# power.net
KiCad netlist of a schematic drawn in Altium Designer
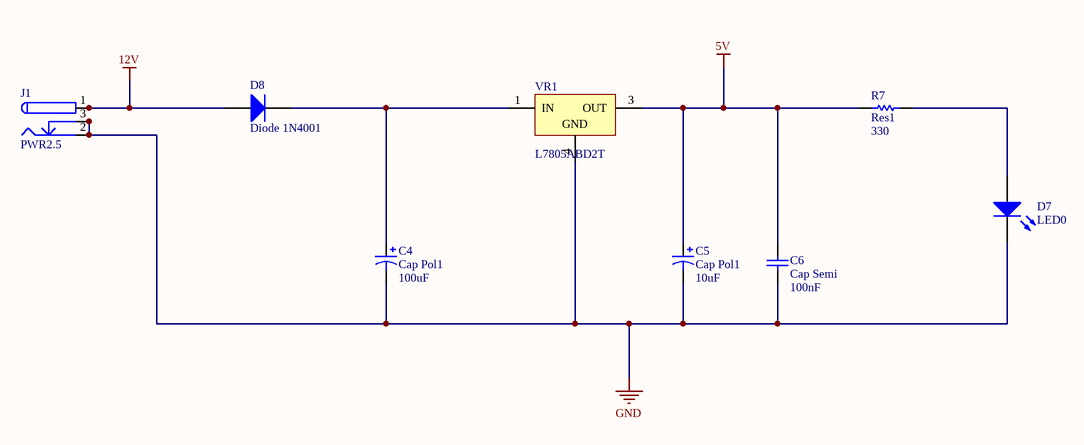
[diagram p0: power.SchDoc]

(export (version "E")
  (design (tool "Eeschema 10.0.6"))
  (components
    (comp (ref "C4")
      (value "Cap Pol1")
      (footprint "RB7.6-15")
      (description "Polarized Capacitor (Radial)")
      (fields (field (name "ALTIUM_VALUE") "100uF") (field (name "PUBLISHER") "Altium Limited"))
      (libsource (lib "Miscellaneous Devices") (part "Cap Pol1"))
    )
    (comp (ref "C5")
      (value "Cap Pol1")
      (footprint "RB7.6-15")
      (description "Polarized Capacitor (Radial)")
      (fields (field (name "ALTIUM_VALUE") "10uF") (field (name "PUBLISHER") "Altium Limited"))
      (libsource (lib "Miscellaneous Devices") (part "Cap Pol1"))
    )
    (comp (ref "C6")
      (value "Cap Semi")
      (footprint "C1206")
      (description "Capacitor (Semiconductor SIM Model)")
      (fields (field (name "ALTIUM_VALUE") "100nF") (field (name "PUBLISHER") "Altium Limited"))
      (libsource (lib "Miscellaneous Devices") (part "Cap Semi"))
    )
    (comp (ref "D7")
      (value "LED0")
      (footprint "LED-0")
      (description "Typical INFRARED GaAs LED")
      (fields (field (name "PUBLISHER") "Altium Limited"))
      (libsource (lib "Miscellaneous Devices") (part "LED0"))
    )
    (comp (ref "D8")
      (value "Diode 1N4001")
      (footprint "DO-41")
      (description "1 Amp General Purpose Rectifier")
      (fields (field (name "PUBLISHER") "Altium Limited"))
      (libsource (lib "Miscellaneous Devices") (part "Diode 1N4001"))
    )
    (comp (ref "J1")
      (value "PWR2.5")
      (footprint "KLD-0202")
      (description "Low Voltage Power Supply Connector")
      (fields (field (name "PUBLISHER") "Altium Limited"))
      (libsource (lib "Miscellaneous Connectors") (part "PWR2.5"))
    )
    (comp (ref "R7")
      (value "Res1")
      (footprint "AXIAL-0.3")
      (description "Resistor")
      (fields (field (name "ALTIUM_VALUE") "330") (field (name "PUBLISHER") "Altium Limited"))
      (libsource (lib "Miscellaneous Devices") (part "Res1"))
    )
    (comp (ref "VR1")
      (value "L7805ABD2T")
      (footprint "TO-263")
      (description "Precision 1A Regulator")
      (fields (field (name "PUBLISHER") "Altium Limited"))
      (libsource (lib "ST Power Mgt Voltage Regulator") (part "L7805ABD2T"))
    )
  )
  (nets
    (net (code "1") (name "5V") (class "Default")
      (node (ref "C5") (pin "1") (pinfunction "1_1") (pintype "passive"))
      (node (ref "C6") (pin "2") (pinfunction "2_2") (pintype "passive"))
      (node (ref "R7") (pin "1") (pinfunction "1_1") (pintype "passive"))
      (node (ref "VR1") (pin "3") (pinfunction "OUT_3") (pintype "power_in"))
    )
    (net (code "2") (name "12V") (class "Default")
      (node (ref "D8") (pin "1") (pinfunction "A_1") (pintype "passive"))
      (node (ref "J1") (pin "1") (pinfunction "1_1") (pintype "power_in"))
      (node (ref "J1") (pin "1A") (pinfunction "1A_1A") (pintype "power_in"))
      (node (ref "J1") (pin "1B") (pinfunction "1B_1B") (pintype "power_in"))
    )
    (net (code "3") (name "GND") (class "Default")
      (node (ref "C4") (pin "2") (pinfunction "2_2") (pintype "passive"))
      (node (ref "C5") (pin "2") (pinfunction "2_2") (pintype "passive"))
      (node (ref "C6") (pin "1") (pinfunction "1_1") (pintype "passive"))
      (node (ref "D7") (pin "2") (pinfunction "K_2") (pintype "passive"))
      (node (ref "J1") (pin "2") (pinfunction "2_2") (pintype "power_in"))
      (node (ref "J1") (pin "2A") (pinfunction "2A_2A") (pintype "power_in"))
      (node (ref "J1") (pin "2B") (pinfunction "2B_2B") (pintype "power_in"))
      (node (ref "J1") (pin "3") (pinfunction "3_3") (pintype "power_in"))
      (node (ref "J1") (pin "3A") (pinfunction "3A_3A") (pintype "power_in"))
      (node (ref "J1") (pin "3B") (pinfunction "3B_3B") (pintype "power_in"))
      (node (ref "VR1") (pin "4") (pinfunction "GND_4") (pintype "power_in"))
    )
    (net (code "4") (name "Net-(D7-A)") (class "Default")
      (node (ref "D7") (pin "1") (pinfunction "A_1") (pintype "passive"))
      (node (ref "R7") (pin "2") (pinfunction "2_2") (pintype "passive"))
    )
    (net (code "5") (name "Net-(D8-K)") (class "Default")
      (node (ref "C4") (pin "1") (pinfunction "1_1") (pintype "passive"))
      (node (ref "D8") (pin "2") (pinfunction "K_2") (pintype "passive"))
      (node (ref "VR1") (pin "1") (pinfunction "IN_1") (pintype "power_in"))
    )
  )
)
